# Sheet1.net
KiCad netlist of a schematic drawn in Altium Designer
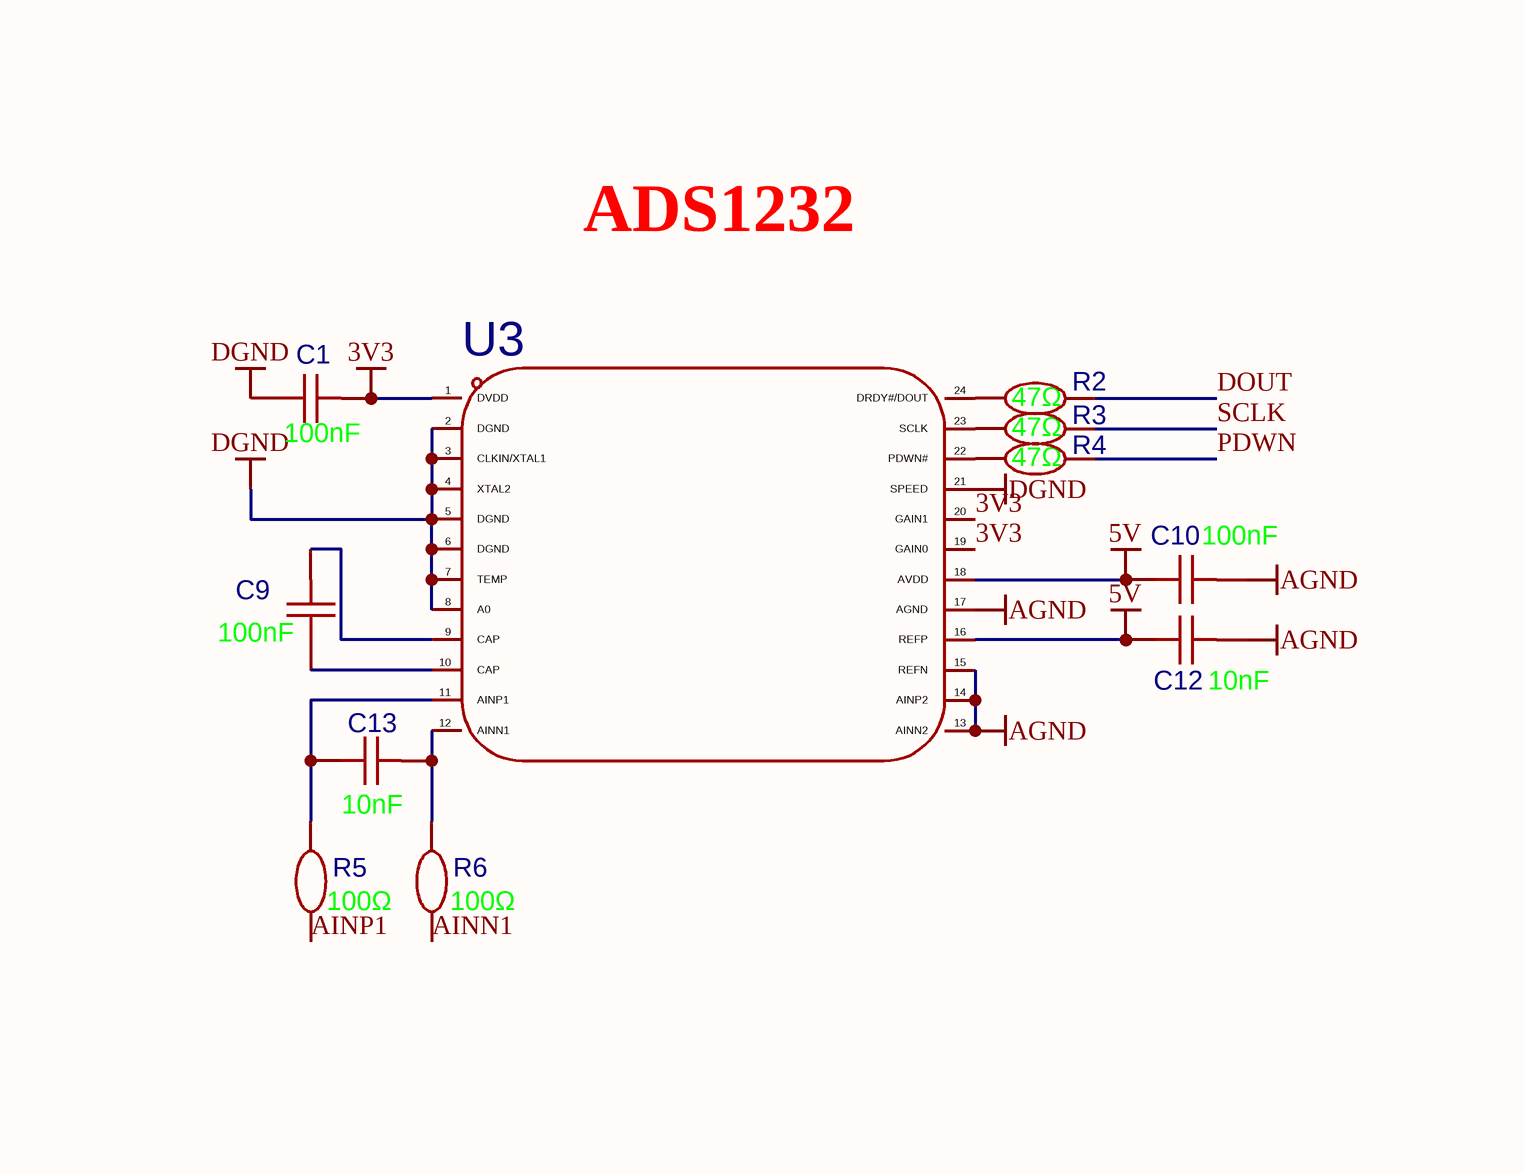
[diagram p0: Sheet1.SchDoc, top left]
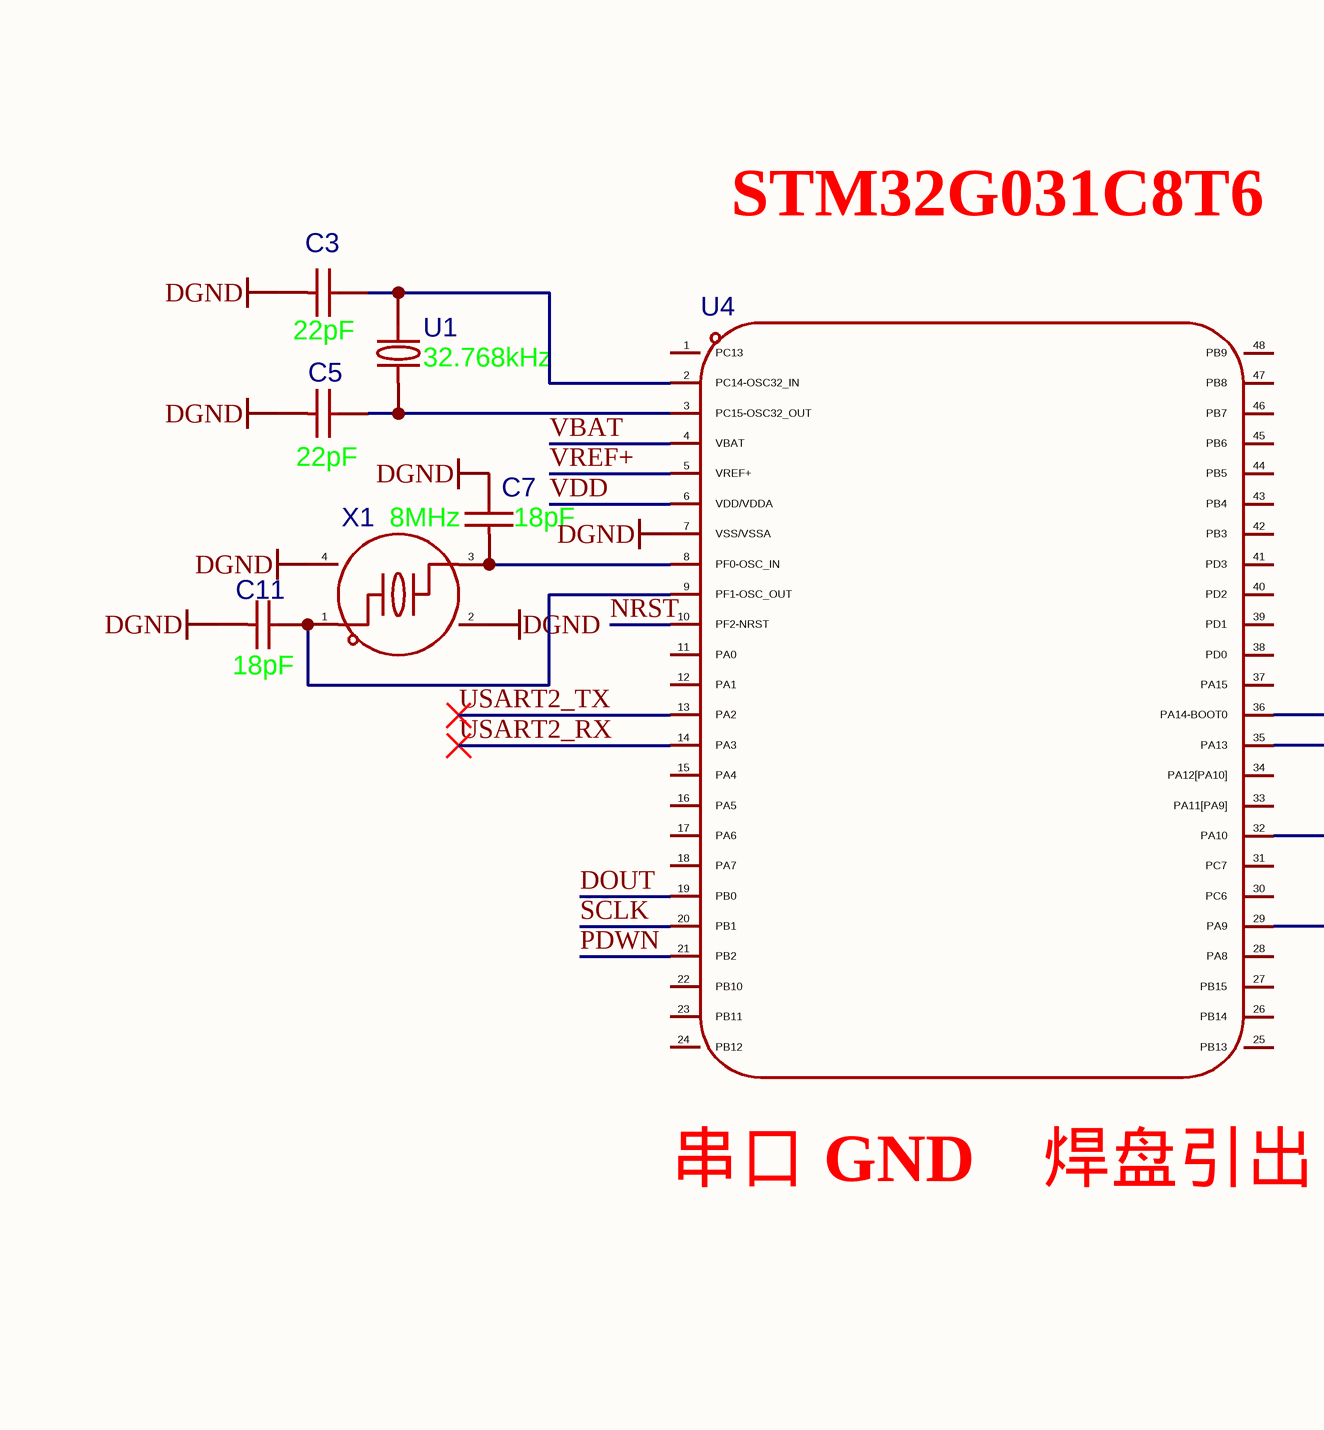
[diagram p1: Sheet1.SchDoc, top middle]
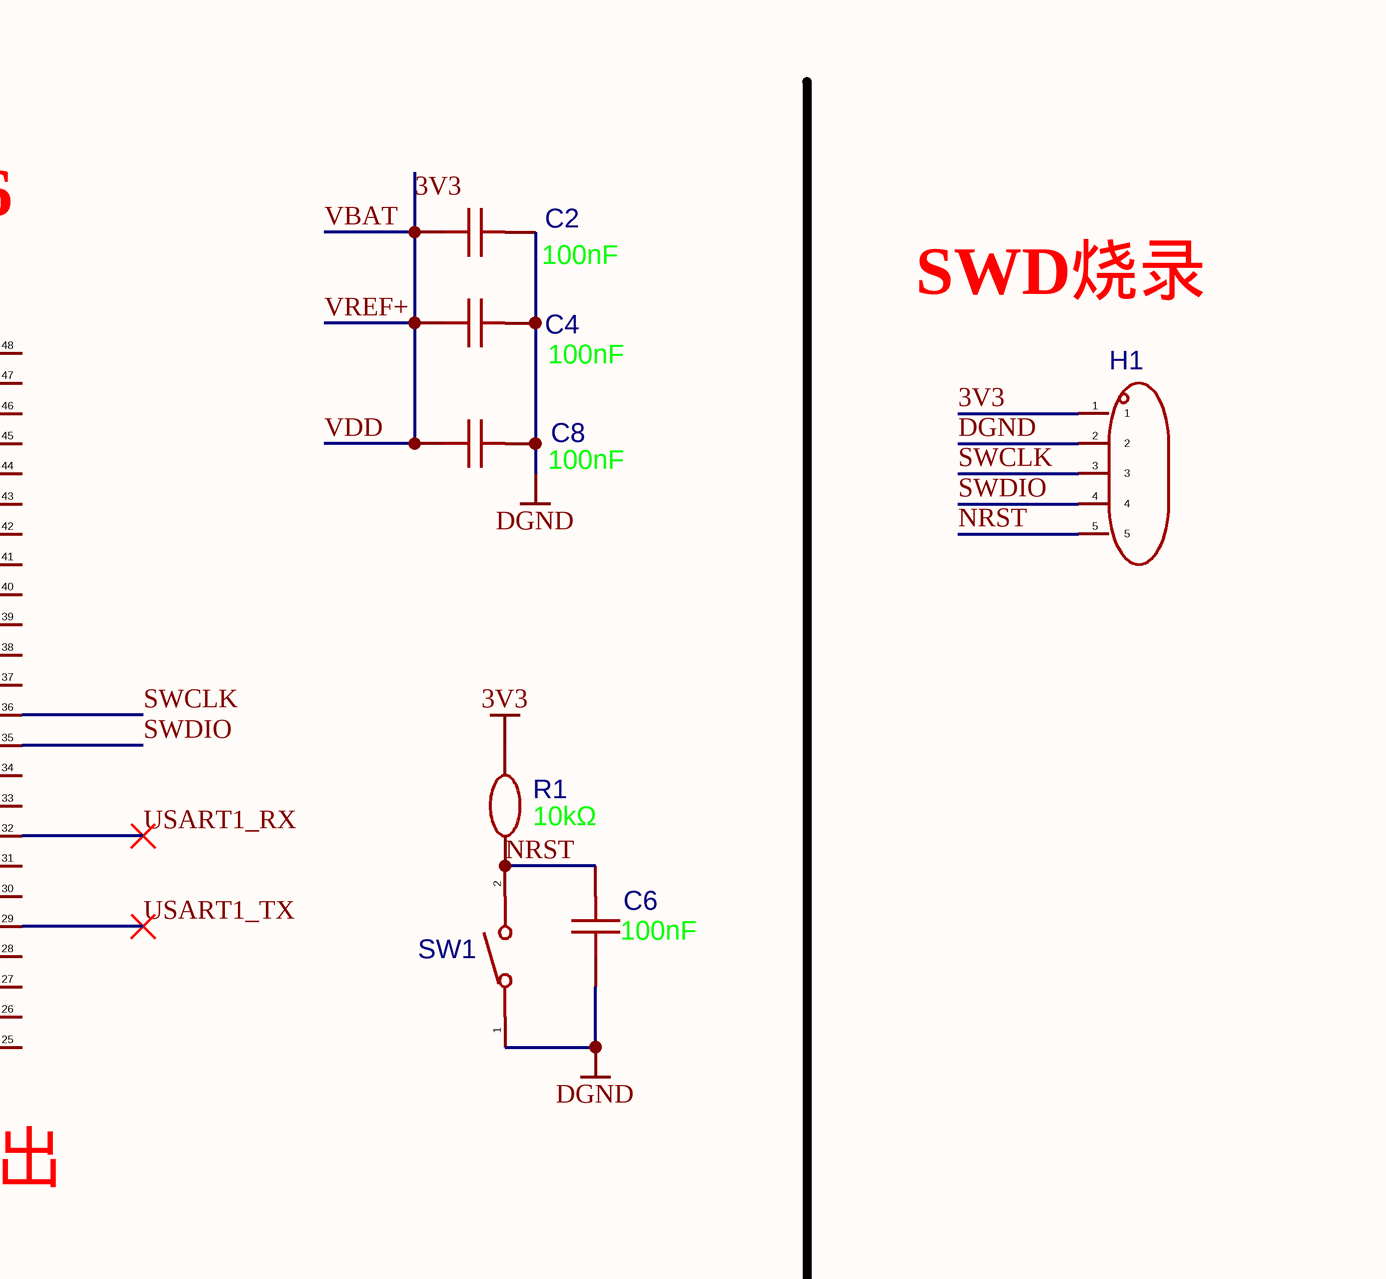
[diagram p2: Sheet1.SchDoc, top right]
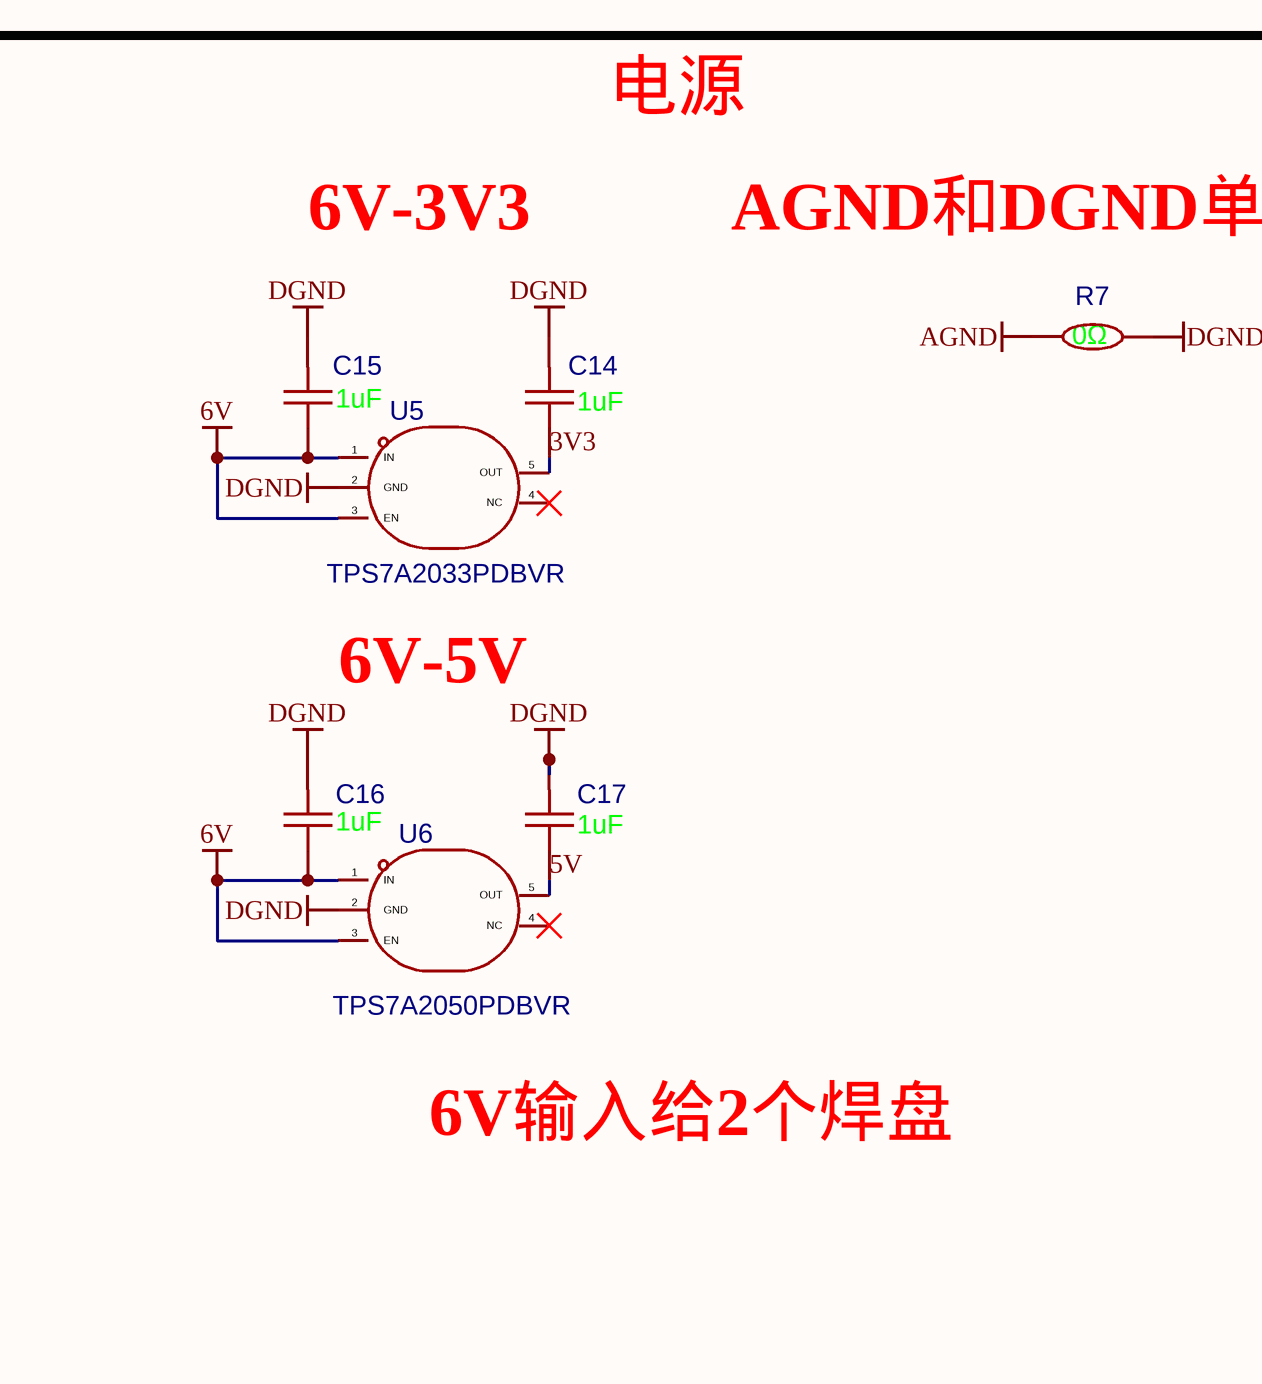
[diagram p3: Sheet1.SchDoc, bottom left]
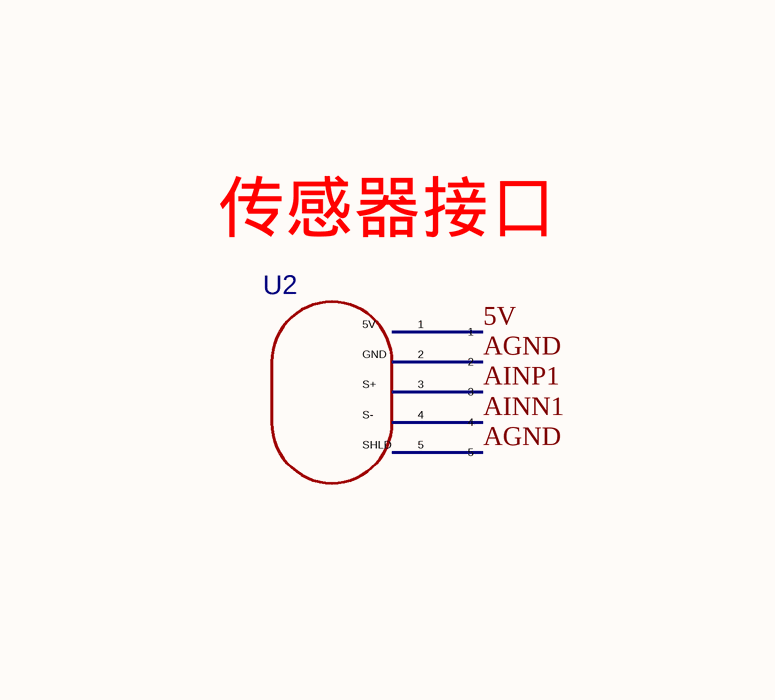
[diagram p4: Sheet1.SchDoc, bottom middle]
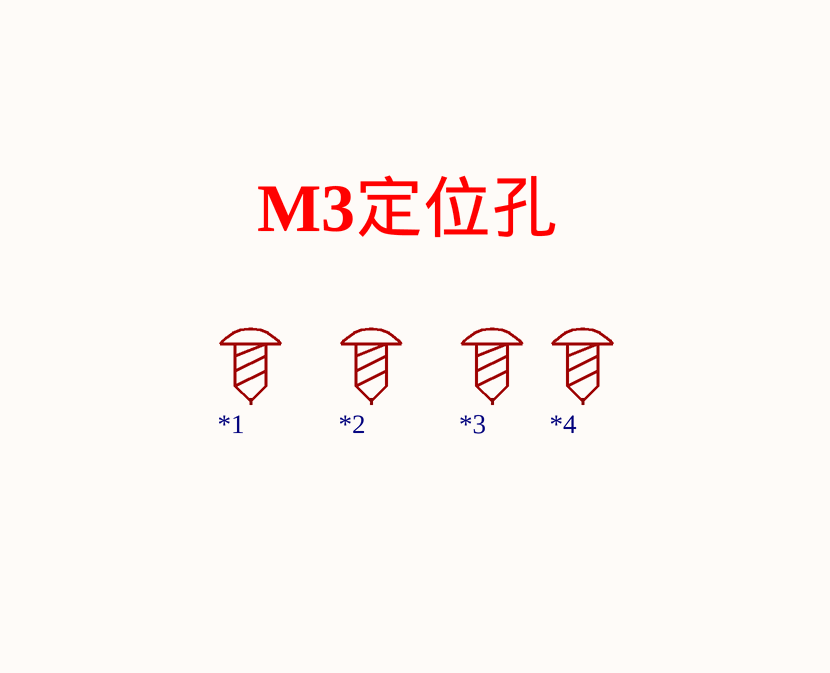
[diagram p5: Sheet1.SchDoc, bottom right]

(export (version "E")
  (design (tool "Eeschema 10.0.6"))
  (components
    (comp (ref "*1") (value "螺丝孔_1") (footprint "M3螺丝") (libsource (lib "螺丝孔_1") (part "螺丝孔_1")))
    (comp (ref "*2") (value "螺丝孔_1") (footprint "M3螺丝") (libsource (lib "螺丝孔_1") (part "螺丝孔_1")))
    (comp (ref "*3") (value "螺丝孔_1") (footprint "M3螺丝") (libsource (lib "螺丝孔_1") (part "螺丝孔_1")))
    (comp (ref "*4") (value "螺丝孔_1") (footprint "M3螺丝") (libsource (lib "螺丝孔_1") (part "螺丝孔_1")))
    (comp (ref "C1")
      (value "100nF")
      (footprint "C0402")
      (description "容值:100nF;精度:±10%;额定电压:16V;温度系数:X7R;")
      (fields (field (name "MANUFACTURER") "YAGEO(国巨)") (field (name "MANUFACTURERPART") "CC0402KRX7R7BB104"))
      (libsource (lib "CC0402KRX7R7BB104") (part "cc0402krx7r7bb104"))
    )
    (comp (ref "C2")
      (value "100nF")
      (footprint "C0402")
      (description "容值:100nF;精度:±10%;额定电压:16V;温度系数:X7R;")
      (fields (field (name "MANUFACTURER") "YAGEO(国巨)") (field (name "MANUFACTURERPART") "CC0402KRX7R7BB104"))
      (libsource (lib "CC0402KRX7R7BB104") (part "cc0402krx7r7bb104"))
    )
    (comp (ref "C3")
      (value "22pF")
      (footprint "C0402")
      (description "容值:22pF;精度:±5%;额定电压:50V;温度系数:NP0;")
      (fields (field (name "MANUFACTURER") "YAGEO(国巨)") (field (name "MANUFACTURERPART") "CC0402JRNPO9BN220"))
      (libsource (lib "CC0402JRNPO9BN220") (part "cc0402jrnpo9bn220"))
    )
    (comp (ref "C4")
      (value "100nF")
      (footprint "C0402")
      (description "容值:100nF;精度:±10%;额定电压:16V;温度系数:X7R;")
      (fields (field (name "MANUFACTURER") "YAGEO(国巨)") (field (name "MANUFACTURERPART") "CC0402KRX7R7BB104"))
      (libsource (lib "CC0402KRX7R7BB104") (part "cc0402krx7r7bb104"))
    )
    (comp (ref "C5")
      (value "22pF")
      (footprint "C0402")
      (description "容值:22pF;精度:±5%;额定电压:50V;温度系数:NP0;")
      (fields (field (name "MANUFACTURER") "YAGEO(国巨)") (field (name "MANUFACTURERPART") "CC0402JRNPO9BN220"))
      (libsource (lib "CC0402JRNPO9BN220") (part "cc0402jrnpo9bn220"))
    )
    (comp (ref "C6")
      (value "100nF")
      (footprint "C0402")
      (description "容值:100nF;精度:±10%;额定电压:16V;温度系数:X7R;")
      (fields (field (name "MANUFACTURER") "YAGEO(国巨)") (field (name "MANUFACTURERPART") "CC0402KRX7R7BB104"))
      (libsource (lib "CC0402KRX7R7BB104") (part "cc0402krx7r7bb104"))
    )
    (comp (ref "C7")
      (value "18pF")
      (footprint "C0402")
      (description "容值:18pF;精度:±5%;额定电压:50V;温度系数:NP0;")
      (fields (field (name "MANUFACTURER") "YAGEO(国巨)") (field (name "MANUFACTURERPART") "CC0402JRNPO9BN180"))
      (libsource (lib "CC0402JRNPO9BN180") (part "cc0402jrnpo9bn180"))
    )
    (comp (ref "C8")
      (value "100nF")
      (footprint "C0402")
      (description "容值:100nF;精度:±10%;额定电压:16V;温度系数:X7R;")
      (fields (field (name "MANUFACTURER") "YAGEO(国巨)") (field (name "MANUFACTURERPART") "CC0402KRX7R7BB104"))
      (libsource (lib "CC0402KRX7R7BB104") (part "cc0402krx7r7bb104"))
    )
    (comp (ref "C9")
      (value "100nF")
      (footprint "C0402")
      (description "容值:100nF;精度:±10%;额定电压:16V;温度系数:X7R;")
      (fields (field (name "MANUFACTURER") "YAGEO(国巨)") (field (name "MANUFACTURERPART") "CC0402KRX7R7BB104"))
      (libsource (lib "CC0402KRX7R7BB104") (part "cc0402krx7r7bb104"))
    )
    (comp (ref "C10")
      (value "100nF")
      (footprint "C0402")
      (description "容值:100nF;精度:±10%;额定电压:16V;温度系数:X7R;")
      (fields (field (name "MANUFACTURER") "YAGEO(国巨)") (field (name "MANUFACTURERPART") "CC0402KRX7R7BB104"))
      (libsource (lib "CC0402KRX7R7BB104") (part "cc0402krx7r7bb104"))
    )
    (comp (ref "C11")
      (value "18pF")
      (footprint "C0402")
      (description "容值:18pF;精度:±5%;额定电压:50V;温度系数:NP0;")
      (fields (field (name "MANUFACTURER") "YAGEO(国巨)") (field (name "MANUFACTURERPART") "CC0402JRNPO9BN180"))
      (libsource (lib "CC0402JRNPO9BN180") (part "cc0402jrnpo9bn180"))
    )
    (comp (ref "C12")
      (value "10nF")
      (footprint "C0402")
      (description "容值:10nF;精度:±10%;额定电压:50V;温度系数:X7R;")
      (fields
        (field (name "MANUFACTURER") "muRata(村田)")
        (field (name "MANUFACTURERPART") "GCM155R71H103KA55D")
      )
      (libsource (lib "GCM155R71H103KA55D") (part "gcm155r71h103ka55d"))
    )
    (comp (ref "C13")
      (value "10nF")
      (footprint "C0402")
      (description "容值:10nF;精度:±10%;额定电压:50V;温度系数:X7R;")
      (fields
        (field (name "MANUFACTURER") "muRata(村田)")
        (field (name "MANUFACTURERPART") "GCM155R71H103KA55D")
      )
      (libsource (lib "GCM155R71H103KA55D") (part "gcm155r71h103ka55d"))
    )
    (comp (ref "C14")
      (value "1uF")
      (footprint "C0603")
      (description "容值:1uF;精度:±10%;额定电压:50V;温度系数:X5R;")
      (fields (field (name "MANUFACTURER") "HRE(芯声)") (field (name "MANUFACTURERPART") "CGA0603X5R105K500JT"))
      (libsource (lib "CGA0603X5R105K500JT") (part "cga0603x5r105k500jt"))
    )
    (comp (ref "C15")
      (value "1uF")
      (footprint "C0603")
      (description "容值:1uF;精度:±10%;额定电压:50V;温度系数:X5R;")
      (fields (field (name "MANUFACTURER") "HRE(芯声)") (field (name "MANUFACTURERPART") "CGA0603X5R105K500JT"))
      (libsource (lib "CGA0603X5R105K500JT") (part "cga0603x5r105k500jt"))
    )
    (comp (ref "C16")
      (value "1uF")
      (footprint "C0603")
      (description "容值:1uF;精度:±10%;额定电压:50V;温度系数:X5R;")
      (fields (field (name "MANUFACTURER") "HRE(芯声)") (field (name "MANUFACTURERPART") "CGA0603X5R105K500JT"))
      (libsource (lib "CGA0603X5R105K500JT") (part "cga0603x5r105k500jt"))
    )
    (comp (ref "C17")
      (value "1uF")
      (footprint "C0603")
      (description "容值:1uF;精度:±10%;额定电压:50V;温度系数:X5R;")
      (fields (field (name "MANUFACTURER") "HRE(芯声)") (field (name "MANUFACTURERPART") "CGA0603X5R105K500JT"))
      (libsource (lib "CGA0603X5R105K500JT") (part "cga0603x5r105k500jt"))
    )
    (comp (ref "H1")
      (value "pz254v-11-05p")
      (footprint "HDR-TH_5P-P2.54-V-M")
      (fields (field (name "MANUFACTURER") "XFCN(兴飞)") (field (name "MANUFACTURERPART") "PZ254V-11-05P"))
      (libsource (lib "PZ254V-11-05P") (part "pz254v-11-05p"))
    )
    (comp (ref "R1")
      (value "10kΩ")
      (footprint "R0603")
      (description "电阻类型:厚膜电阻;阻值:10kΩ;精度:±1%;功率:100mW;工作电压:75V;温度系数:±100ppm/℃;")
      (fields (field (name "MANUFACTURER") "FOJAN(富捷)") (field (name "MANUFACTURERPART") "FRC0603F1002TS"))
      (libsource (lib "FRC0603F1002TS") (part "frc0603f1002ts"))
    )
    (comp (ref "R2")
      (value "47Ω")
      (footprint "R0402")
      (description "电阻类型:厚膜电阻;阻值:47Ω;精度:±1%;功率:62.5mW;工作电压:50V;温度系数:±100ppm/℃;")
      (fields (field (name "MANUFACTURER") "FOJAN(富捷)") (field (name "MANUFACTURERPART") "FRC0402F47R0TS"))
      (libsource (lib "FRC0402F47R0TS") (part "frc0402f47r0ts"))
    )
    (comp (ref "R3")
      (value "47Ω")
      (footprint "R0402")
      (description "电阻类型:厚膜电阻;阻值:47Ω;精度:±1%;功率:62.5mW;工作电压:50V;温度系数:±100ppm/℃;")
      (fields (field (name "MANUFACTURER") "FOJAN(富捷)") (field (name "MANUFACTURERPART") "FRC0402F47R0TS"))
      (libsource (lib "FRC0402F47R0TS") (part "frc0402f47r0ts"))
    )
    (comp (ref "R4")
      (value "47Ω")
      (footprint "R0402")
      (description "电阻类型:厚膜电阻;阻值:47Ω;精度:±1%;功率:62.5mW;工作电压:50V;温度系数:±100ppm/℃;")
      (fields (field (name "MANUFACTURER") "FOJAN(富捷)") (field (name "MANUFACTURERPART") "FRC0402F47R0TS"))
      (libsource (lib "FRC0402F47R0TS") (part "frc0402f47r0ts"))
    )
    (comp (ref "R5")
      (value "100Ω")
      (footprint "R0402")
      (description "电阻类型:厚膜电阻;阻值:100Ω;精度:±1%;功率:62.5mW;工作电压:50V;温度系数:±100ppm/℃;")
      (fields (field (name "MANUFACTURER") "FOJAN(富捷)") (field (name "MANUFACTURERPART") "FRC0402F1000TS"))
      (libsource (lib "FRC0402F1000TS") (part "frc0402f1000ts"))
    )
    (comp (ref "R6")
      (value "100Ω")
      (footprint "R0402")
      (description "电阻类型:厚膜电阻;阻值:100Ω;精度:±1%;功率:62.5mW;工作电压:50V;温度系数:±100ppm/℃;")
      (fields (field (name "MANUFACTURER") "FOJAN(富捷)") (field (name "MANUFACTURERPART") "FRC0402F1000TS"))
      (libsource (lib "FRC0402F1000TS") (part "frc0402f1000ts"))
    )
    (comp (ref "R7")
      (value "0Ω")
      (footprint "R0603")
      (description "电阻类型:厚膜电阻;阻值:0Ω;精度:±1%;功率:100mW;工作电压:75V;温度系数:-;")
      (fields
        (field (name "MANUFACTURER") "UNI-ROYAL(厚声)")
        (field (name "MANUFACTURERPART") "0603WAF0000T5E")
      )
      (libsource (lib "0603WAF0000T5E") (part "0603waf0000t5e"))
    )
    (comp (ref "SW1")
      (value "ts-1088-ar02016")
      (footprint "SW-SMD_L3.9-W3.0-P4.45")
      (fields (field (name "MANUFACTURER") "XUNPU(讯普)") (field (name "MANUFACTURERPART") "TS-1088-AR02016"))
      (libsource (lib "TS-1088-AR02016") (part "ts-1088-ar02016"))
    )
    (comp (ref "U1")
      (value "32.768kHz")
      (footprint "CRYSTAL-SMD_L3.2-W1.5")
      (description "晶振类型:贴片晶振;频率:32.768kHz;常温频差:±10ppm;负载电容:12.5pF;频率稳定度:±10ppm;")
      (fields
        (field (name "MANUFACTURER") "HCI(杭晶)")
        (field (name "MANUFACTURERPART") "FC31M2-32.768-NTLNNDTL")
      )
      (libsource (lib "FC31M2-32.768-NTLNNDTL") (part "fc31m2-32.768-ntlnndtl"))
    )
    (comp (ref "U2") (value "5个焊盘") (footprint "5个焊盘") (libsource (lib "5个焊盘") (part "5个焊盘")))
    (comp (ref "U3")
      (value "ads1232ipwr")
      (footprint "TSSOP-24_L7.8-W4.4-P0.65-LS6.4-BL")
      (description "分辨率(位):24;采样率:10Hz;工作电压:2.7V~5.3V;接口类型:SPI;")
      (fields (field (name "MANUFACTURER") "TI(德州仪器)") (field (name "MANUFACTURERPART") "ADS1232IPWR"))
      (libsource (lib "ADS1232IPW") (part "ads1232ipwr"))
    )
    (comp (ref "U4")
      (value "stm32g031c8t6")
      (footprint "LQFP-48_L7.0-W7.0-P0.50-LS9.0-BL")
      (description "CPU内核:ARM Cortex-M0+;CPU最大主频:64MHz;CPU位数:32 Bit;")
      (fields (field (name "MANUFACTURER") "ST(意法半导体)") (field (name "MANUFACTURERPART") "STM32G031C8T6"))
      (libsource (lib "STM32G031C8T6") (part "stm32g031c8t6"))
    )
    (comp (ref "U5")
      (value "tps7a2033pdbvr")
      (footprint "SOT-23-5_L2.9-W1.6-P0.95-LS2.8-BR")
      (description "输出类型:固定;最大输入电压:6V;输出电压:3.3V;输出电流:300mA;输出极性:正极;")
      (fields
        (field (name "SYMBOL") "TPS7A2033PDBVR")
        (field (name "MANUFACTURER") "TI(德州仪器)")
        (field (name "MANUFACTURERPART") "TPS7A2033PDBVR")
      )
      (libsource (lib "TPS7A2033PDBVR") (part "tps7a2033pdbvr"))
    )
    (comp (ref "U6")
      (value "tps7a2050pdbvr")
      (footprint "SOT-23-5_L2.9-W1.6-P0.95-LS2.8-BR")
      (description "输出极性:正极;工作电压:6V;输出电压:5V;输出电流:300mA;电源纹波抑制比(PSRR):65dB@(100Hz);输出类型:固定;")
      (fields
        (field (name "SYMBOL") "TPS7A2050PDBVR")
        (field (name "MANUFACTURER") "TI(德州仪器)")
        (field (name "MANUFACTURERPART") "TPS7A2050PDBVR")
      )
      (libsource (lib "TPS7A2050PDBVR") (part "tps7a2050pdbvr"))
    )
    (comp (ref "X1")
      (value "8MHz")
      (footprint "CRYSTAL-SMD_4P-L3.2-W2.5-BL")
      (description "晶振类型:贴片晶振;频率:8MHz;常温频差:±10ppm;负载电容:12pF;频率稳定度:±20ppm;")
      (fields (field (name "MANUFACTURER") "YXC(扬兴晶振)") (field (name "MANUFACTURERPART") "X32258MOB4SI"))
      (libsource (lib "X32258MOB4SI") (part "x32258mob4si"))
    )
  )
  (nets
    (net (code "1") (name "/AINN1") (class "Default")
      (node (ref "R6") (pin "1") (pinfunction "1_1") (pintype "passive"))
      (node (ref "U2") (pin "4") (pinfunction "4_4") (pintype "passive"))
    )
    (net (code "2") (name "/AINP1") (class "Default")
      (node (ref "R5") (pin "1") (pinfunction "1_1") (pintype "passive"))
      (node (ref "U2") (pin "3") (pinfunction "3_3") (pintype "passive"))
    )
    (net (code "3") (name "/DOUT") (class "Default")
      (node (ref "R2") (pin "2") (pinfunction "2_2") (pintype "passive"))
      (node (ref "U4") (pin "19") (pinfunction "PB0_19") (pintype "passive"))
    )
    (net (code "4") (name "/NRST") (class "Default")
      (node (ref "C6") (pin "2") (pinfunction "2_2") (pintype "passive"))
      (node (ref "H1") (pin "5") (pinfunction "5_5") (pintype "passive"))
      (node (ref "R1") (pin "1") (pinfunction "1_1") (pintype "passive"))
      (node (ref "SW1") (pin "2") (pinfunction "2_2") (pintype "passive"))
      (node (ref "U4") (pin "10") (pinfunction "PF2-NRST_10") (pintype "passive"))
    )
    (net (code "5") (name "/PDWN") (class "Default")
      (node (ref "R4") (pin "2") (pinfunction "2_2") (pintype "passive"))
      (node (ref "U4") (pin "21") (pinfunction "PB2_21") (pintype "passive"))
    )
    (net (code "6") (name "/SCLK") (class "Default")
      (node (ref "R3") (pin "2") (pinfunction "2_2") (pintype "passive"))
      (node (ref "U4") (pin "20") (pinfunction "PB1_20") (pintype "passive"))
    )
    (net (code "7") (name "/SWCLK") (class "Default")
      (node (ref "H1") (pin "3") (pinfunction "3_3") (pintype "passive"))
      (node (ref "U4") (pin "36") (pinfunction "PA14-BOOT0_36") (pintype "passive"))
    )
    (net (code "8") (name "/SWDIO") (class "Default")
      (node (ref "H1") (pin "4") (pinfunction "4_4") (pintype "passive"))
      (node (ref "U4") (pin "35") (pinfunction "PA13_35") (pintype "passive"))
    )
    (net (code "9") (name "/USART1_RX") (class "Default")
      (node (ref "U4") (pin "32") (pinfunction "PA10_32") (pintype "passive+no_connect"))
    )
    (net (code "10") (name "/USART1_TX") (class "Default")
      (node (ref "U4") (pin "29") (pinfunction "PA9_29") (pintype "passive+no_connect"))
    )
    (net (code "11") (name "/USART2_RX") (class "Default")
      (node (ref "U4") (pin "14") (pinfunction "PA3_14") (pintype "passive+no_connect"))
    )
    (net (code "12") (name "/USART2_TX") (class "Default")
      (node (ref "U4") (pin "13") (pinfunction "PA2_13") (pintype "passive+no_connect"))
    )
    (net (code "13") (name "3V3") (class "Default")
      (node (ref "C1") (pin "2") (pinfunction "2_2") (pintype "passive"))
      (node (ref "C14") (pin "1") (pinfunction "1_1") (pintype "passive"))
      (node (ref "C2") (pin "1") (pinfunction "1_1") (pintype "passive"))
      (node (ref "C4") (pin "1") (pinfunction "1_1") (pintype "passive"))
      (node (ref "C8") (pin "1") (pinfunction "1_1") (pintype "passive"))
      (node (ref "H1") (pin "1") (pinfunction "1_1") (pintype "passive"))
      (node (ref "R1") (pin "2") (pinfunction "2_2") (pintype "passive"))
      (node (ref "U3") (pin "1") (pinfunction "DVDD_1") (pintype "passive"))
      (node (ref "U3") (pin "19") (pinfunction "GAIN0_19") (pintype "passive"))
      (node (ref "U3") (pin "20") (pinfunction "GAIN1_20") (pintype "passive"))
      (node (ref "U4") (pin "4") (pinfunction "VBAT_4") (pintype "passive"))
      (node (ref "U4") (pin "5") (pinfunction "VREF+_5") (pintype "passive"))
      (node (ref "U4") (pin "6") (pinfunction "VDD/VDDA_6") (pintype "passive"))
      (node (ref "U5") (pin "5") (pinfunction "OUT_5") (pintype "passive"))
    )
    (net (code "14") (name "5V") (class "Default")
      (node (ref "C10") (pin "1") (pinfunction "1_1") (pintype "passive"))
      (node (ref "C12") (pin "1") (pinfunction "1_1") (pintype "passive"))
      (node (ref "C17") (pin "1") (pinfunction "1_1") (pintype "passive"))
      (node (ref "U2") (pin "1") (pinfunction "1_1") (pintype "passive"))
      (node (ref "U3") (pin "16") (pinfunction "REFP_16") (pintype "passive"))
      (node (ref "U3") (pin "18") (pinfunction "AVDD_18") (pintype "passive"))
      (node (ref "U6") (pin "5") (pinfunction "OUT_5") (pintype "passive"))
    )
    (net (code "15") (name "6V") (class "Default")
      (node (ref "C15") (pin "1") (pinfunction "1_1") (pintype "passive"))
      (node (ref "C16") (pin "1") (pinfunction "1_1") (pintype "passive"))
      (node (ref "U5") (pin "1") (pinfunction "IN_1") (pintype "passive"))
      (node (ref "U5") (pin "3") (pinfunction "EN_3") (pintype "passive"))
      (node (ref "U6") (pin "1") (pinfunction "IN_1") (pintype "passive"))
      (node (ref "U6") (pin "3") (pinfunction "EN_3") (pintype "passive"))
    )
    (net (code "16") (name "AGND") (class "Default")
      (node (ref "C10") (pin "2") (pinfunction "2_2") (pintype "passive"))
      (node (ref "C12") (pin "2") (pinfunction "2_2") (pintype "passive"))
      (node (ref "R7") (pin "1") (pinfunction "1_1") (pintype "passive"))
      (node (ref "U2") (pin "2") (pinfunction "2_2") (pintype "passive"))
      (node (ref "U2") (pin "5") (pinfunction "5_5") (pintype "passive"))
      (node (ref "U3") (pin "13") (pinfunction "AINN2_13") (pintype "passive"))
      (node (ref "U3") (pin "14") (pinfunction "AINP2_14") (pintype "passive"))
      (node (ref "U3") (pin "15") (pinfunction "REFN_15") (pintype "passive"))
      (node (ref "U3") (pin "17") (pinfunction "AGND_17") (pintype "passive"))
    )
    (net (code "17") (name "DGND") (class "Default")
      (node (ref "C1") (pin "1") (pinfunction "1_1") (pintype "passive"))
      (node (ref "C11") (pin "1") (pinfunction "1_1") (pintype "passive"))
      (node (ref "C14") (pin "2") (pinfunction "2_2") (pintype "passive"))
      (node (ref "C15") (pin "2") (pinfunction "2_2") (pintype "passive"))
      (node (ref "C16") (pin "2") (pinfunction "2_2") (pintype "passive"))
      (node (ref "C17") (pin "2") (pinfunction "2_2") (pintype "passive"))
      (node (ref "C2") (pin "2") (pinfunction "2_2") (pintype "passive"))
      (node (ref "C3") (pin "1") (pinfunction "1_1") (pintype "passive"))
      (node (ref "C4") (pin "2") (pinfunction "2_2") (pintype "passive"))
      (node (ref "C5") (pin "1") (pinfunction "1_1") (pintype "passive"))
      (node (ref "C6") (pin "1") (pinfunction "1_1") (pintype "passive"))
      (node (ref "C7") (pin "2") (pinfunction "2_2") (pintype "passive"))
      (node (ref "C8") (pin "2") (pinfunction "2_2") (pintype "passive"))
      (node (ref "H1") (pin "2") (pinfunction "2_2") (pintype "passive"))
      (node (ref "R7") (pin "2") (pinfunction "2_2") (pintype "passive"))
      (node (ref "SW1") (pin "1") (pinfunction "1_1") (pintype "passive"))
      (node (ref "U3") (pin "2") (pinfunction "DGND_2") (pintype "passive"))
      (node (ref "U3") (pin "21") (pinfunction "SPEED_21") (pintype "passive"))
      (node (ref "U3") (pin "3") (pinfunction "CLKIN/XTAL1_3") (pintype "passive"))
      (node (ref "U3") (pin "4") (pinfunction "XTAL2_4") (pintype "passive"))
      (node (ref "U3") (pin "5") (pinfunction "DGND_5") (pintype "passive"))
      (node (ref "U3") (pin "6") (pinfunction "DGND_6") (pintype "passive"))
      (node (ref "U3") (pin "7") (pinfunction "TEMP_7") (pintype "passive"))
      (node (ref "U3") (pin "8") (pinfunction "A0_8") (pintype "passive"))
      (node (ref "U4") (pin "7") (pinfunction "VSS/VSSA_7") (pintype "passive"))
      (node (ref "U5") (pin "2") (pinfunction "GND_2") (pintype "passive"))
      (node (ref "U6") (pin "2") (pinfunction "GND_2") (pintype "passive"))
      (node (ref "X1") (pin "2") (pinfunction "GND_2") (pintype "passive"))
      (node (ref "X1") (pin "4") (pinfunction "GND_4") (pintype "passive"))
    )
    (net (code "18") (name "Net-(C9-Pad1)") (class "Default")
      (node (ref "C9") (pin "1") (pinfunction "1_1") (pintype "passive"))
      (node (ref "U3") (pin "10") (pinfunction "CAP_10") (pintype "passive"))
    )
    (net (code "19") (name "Net-(C9-Pad2)") (class "Default")
      (node (ref "C9") (pin "2") (pinfunction "2_2") (pintype "passive"))
      (node (ref "U3") (pin "9") (pinfunction "CAP_9") (pintype "passive"))
    )
    (net (code "20") (name "Net-(U3-AINN1)") (class "Default")
      (node (ref "C13") (pin "2") (pinfunction "2_2") (pintype "passive"))
      (node (ref "R6") (pin "2") (pinfunction "2_2") (pintype "passive"))
      (node (ref "U3") (pin "12") (pinfunction "AINN1_12") (pintype "passive"))
    )
    (net (code "21") (name "Net-(U3-AINP1)") (class "Default")
      (node (ref "C13") (pin "1") (pinfunction "1_1") (pintype "passive"))
      (node (ref "R5") (pin "2") (pinfunction "2_2") (pintype "passive"))
      (node (ref "U3") (pin "11") (pinfunction "AINP1_11") (pintype "passive"))
    )
    (net (code "22") (name "Net-(U3-DRDY#{slash}DOUT)") (class "Default")
      (node (ref "R2") (pin "1") (pinfunction "1_1") (pintype "passive"))
      (node (ref "U3") (pin "24") (pinfunction "DRDY#/DOUT_24") (pintype "passive"))
    )
    (net (code "23") (name "Net-(U3-PDWN#)") (class "Default")
      (node (ref "R4") (pin "1") (pinfunction "1_1") (pintype "passive"))
      (node (ref "U3") (pin "22") (pinfunction "PDWN#_22") (pintype "passive"))
    )
    (net (code "24") (name "Net-(U3-SCLK)") (class "Default")
      (node (ref "R3") (pin "1") (pinfunction "1_1") (pintype "passive"))
      (node (ref "U3") (pin "23") (pinfunction "SCLK_23") (pintype "passive"))
    )
    (net (code "25") (name "Net-(U4-PC14-OSC32_IN)") (class "Default")
      (node (ref "C3") (pin "2") (pinfunction "2_2") (pintype "passive"))
      (node (ref "U1") (pin "2") (pinfunction "2_2") (pintype "passive"))
      (node (ref "U4") (pin "2") (pinfunction "PC14-OSC32_IN_2") (pintype "passive"))
    )
    (net (code "26") (name "Net-(U4-PC15-OSC32_OUT)") (class "Default")
      (node (ref "C5") (pin "2") (pinfunction "2_2") (pintype "passive"))
      (node (ref "U1") (pin "1") (pinfunction "1_1") (pintype "passive"))
      (node (ref "U4") (pin "3") (pinfunction "PC15-OSC32_OUT_3") (pintype "passive"))
    )
    (net (code "27") (name "Net-(U4-PF0-OSC_IN)") (class "Default")
      (node (ref "C7") (pin "1") (pinfunction "1_1") (pintype "passive"))
      (node (ref "U4") (pin "8") (pinfunction "PF0-OSC_IN_8") (pintype "passive"))
      (node (ref "X1") (pin "3") (pinfunction "3_3") (pintype "passive"))
    )
    (net (code "28") (name "Net-(U4-PF1-OSC_OUT)") (class "Default")
      (node (ref "C11") (pin "2") (pinfunction "2_2") (pintype "passive"))
      (node (ref "U4") (pin "9") (pinfunction "PF1-OSC_OUT_9") (pintype "passive"))
      (node (ref "X1") (pin "1") (pinfunction "1_1") (pintype "passive"))
    )
    (net (code "29") (name "unconnected-(*1-Pad1)") (class "Default")
      (node (ref "*1") (pin "1") (pinfunction "1_1") (pintype "passive"))
    )
    (net (code "30") (name "unconnected-(*2-Pad1)") (class "Default")
      (node (ref "*2") (pin "1") (pinfunction "1_1") (pintype "passive"))
    )
    (net (code "31") (name "unconnected-(*3-Pad1)") (class "Default")
      (node (ref "*3") (pin "1") (pinfunction "1_1") (pintype "passive"))
    )
    (net (code "32") (name "unconnected-(*4-Pad1)") (class "Default")
      (node (ref "*4") (pin "1") (pinfunction "1_1") (pintype "passive"))
    )
    (net (code "33") (name "unconnected-(U4-PA0-Pad11)") (class "Default")
      (node (ref "U4") (pin "11") (pinfunction "PA0_11") (pintype "passive"))
    )
    (net (code "34") (name "unconnected-(U4-PA1-Pad12)") (class "Default")
      (node (ref "U4") (pin "12") (pinfunction "PA1_12") (pintype "passive"))
    )
    (net (code "35") (name "unconnected-(U4-PA4-Pad15)") (class "Default")
      (node (ref "U4") (pin "15") (pinfunction "PA4_15") (pintype "passive"))
    )
    (net (code "36") (name "unconnected-(U4-PA5-Pad16)") (class "Default")
      (node (ref "U4") (pin "16") (pinfunction "PA5_16") (pintype "passive"))
    )
    (net (code "37") (name "unconnected-(U4-PA6-Pad17)") (class "Default")
      (node (ref "U4") (pin "17") (pinfunction "PA6_17") (pintype "passive"))
    )
    (net (code "38") (name "unconnected-(U4-PA7-Pad18)") (class "Default")
      (node (ref "U4") (pin "18") (pinfunction "PA7_18") (pintype "passive"))
    )
    (net (code "39") (name "unconnected-(U4-PA8-Pad28)") (class "Default")
      (node (ref "U4") (pin "28") (pinfunction "PA8_28") (pintype "passive"))
    )
    (net (code "40") (name "unconnected-(U4-PA11[PA9]-Pad33)") (class "Default")
      (node (ref "U4") (pin "33") (pinfunction "PA11[PA9]_33") (pintype "passive"))
    )
    (net (code "41") (name "unconnected-(U4-PA12[PA10]-Pad34)") (class "Default")
      (node (ref "U4") (pin "34") (pinfunction "PA12[PA10]_34") (pintype "passive"))
    )
    (net (code "42") (name "unconnected-(U4-PA15-Pad37)") (class "Default")
      (node (ref "U4") (pin "37") (pinfunction "PA15_37") (pintype "passive"))
    )
    (net (code "43") (name "unconnected-(U4-PB3-Pad42)") (class "Default")
      (node (ref "U4") (pin "42") (pinfunction "PB3_42") (pintype "passive"))
    )
    (net (code "44") (name "unconnected-(U4-PB4-Pad43)") (class "Default")
      (node (ref "U4") (pin "43") (pinfunction "PB4_43") (pintype "passive"))
    )
    (net (code "45") (name "unconnected-(U4-PB5-Pad44)") (class "Default")
      (node (ref "U4") (pin "44") (pinfunction "PB5_44") (pintype "passive"))
    )
    (net (code "46") (name "unconnected-(U4-PB6-Pad45)") (class "Default")
      (node (ref "U4") (pin "45") (pinfunction "PB6_45") (pintype "passive"))
    )
    (net (code "47") (name "unconnected-(U4-PB7-Pad46)") (class "Default")
      (node (ref "U4") (pin "46") (pinfunction "PB7_46") (pintype "passive"))
    )
    (net (code "48") (name "unconnected-(U4-PB8-Pad47)") (class "Default")
      (node (ref "U4") (pin "47") (pinfunction "PB8_47") (pintype "passive"))
    )
    (net (code "49") (name "unconnected-(U4-PB9-Pad48)") (class "Default")
      (node (ref "U4") (pin "48") (pinfunction "PB9_48") (pintype "passive"))
    )
    (net (code "50") (name "unconnected-(U4-PB10-Pad22)") (class "Default")
      (node (ref "U4") (pin "22") (pinfunction "PB10_22") (pintype "passive"))
    )
    (net (code "51") (name "unconnected-(U4-PB11-Pad23)") (class "Default")
      (node (ref "U4") (pin "23") (pinfunction "PB11_23") (pintype "passive"))
    )
    (net (code "52") (name "unconnected-(U4-PB12-Pad24)") (class "Default")
      (node (ref "U4") (pin "24") (pinfunction "PB12_24") (pintype "passive"))
    )
    (net (code "53") (name "unconnected-(U4-PB13-Pad25)") (class "Default")
      (node (ref "U4") (pin "25") (pinfunction "PB13_25") (pintype "passive"))
    )
    (net (code "54") (name "unconnected-(U4-PB14-Pad26)") (class "Default")
      (node (ref "U4") (pin "26") (pinfunction "PB14_26") (pintype "passive"))
    )
    (net (code "55") (name "unconnected-(U4-PB15-Pad27)") (class "Default")
      (node (ref "U4") (pin "27") (pinfunction "PB15_27") (pintype "passive"))
    )
    (net (code "56") (name "unconnected-(U4-PC6-Pad30)") (class "Default")
      (node (ref "U4") (pin "30") (pinfunction "PC6_30") (pintype "passive"))
    )
    (net (code "57") (name "unconnected-(U4-PC7-Pad31)") (class "Default")
      (node (ref "U4") (pin "31") (pinfunction "PC7_31") (pintype "passive"))
    )
    (net (code "58") (name "unconnected-(U4-PC13-Pad1)") (class "Default")
      (node (ref "U4") (pin "1") (pinfunction "PC13_1") (pintype "passive"))
    )
    (net (code "59") (name "unconnected-(U4-PD0-Pad38)") (class "Default")
      (node (ref "U4") (pin "38") (pinfunction "PD0_38") (pintype "passive"))
    )
    (net (code "60") (name "unconnected-(U4-PD1-Pad39)") (class "Default")
      (node (ref "U4") (pin "39") (pinfunction "PD1_39") (pintype "passive"))
    )
    (net (code "61") (name "unconnected-(U4-PD2-Pad40)") (class "Default")
      (node (ref "U4") (pin "40") (pinfunction "PD2_40") (pintype "passive"))
    )
    (net (code "62") (name "unconnected-(U4-PD3-Pad41)") (class "Default")
      (node (ref "U4") (pin "41") (pinfunction "PD3_41") (pintype "passive"))
    )
    (net (code "63") (name "unconnected-(U5-NC-Pad4)") (class "Default")
      (node (ref "U5") (pin "4") (pinfunction "NC_4") (pintype "passive+no_connect"))
    )
    (net (code "64") (name "unconnected-(U6-NC-Pad4)") (class "Default")
      (node (ref "U6") (pin "4") (pinfunction "NC_4") (pintype "passive+no_connect"))
    )
  )
)
